# ESP8266_MySensorsGateway_v1_4.net
KiCad netlist of a schematic drawn in EAGLE
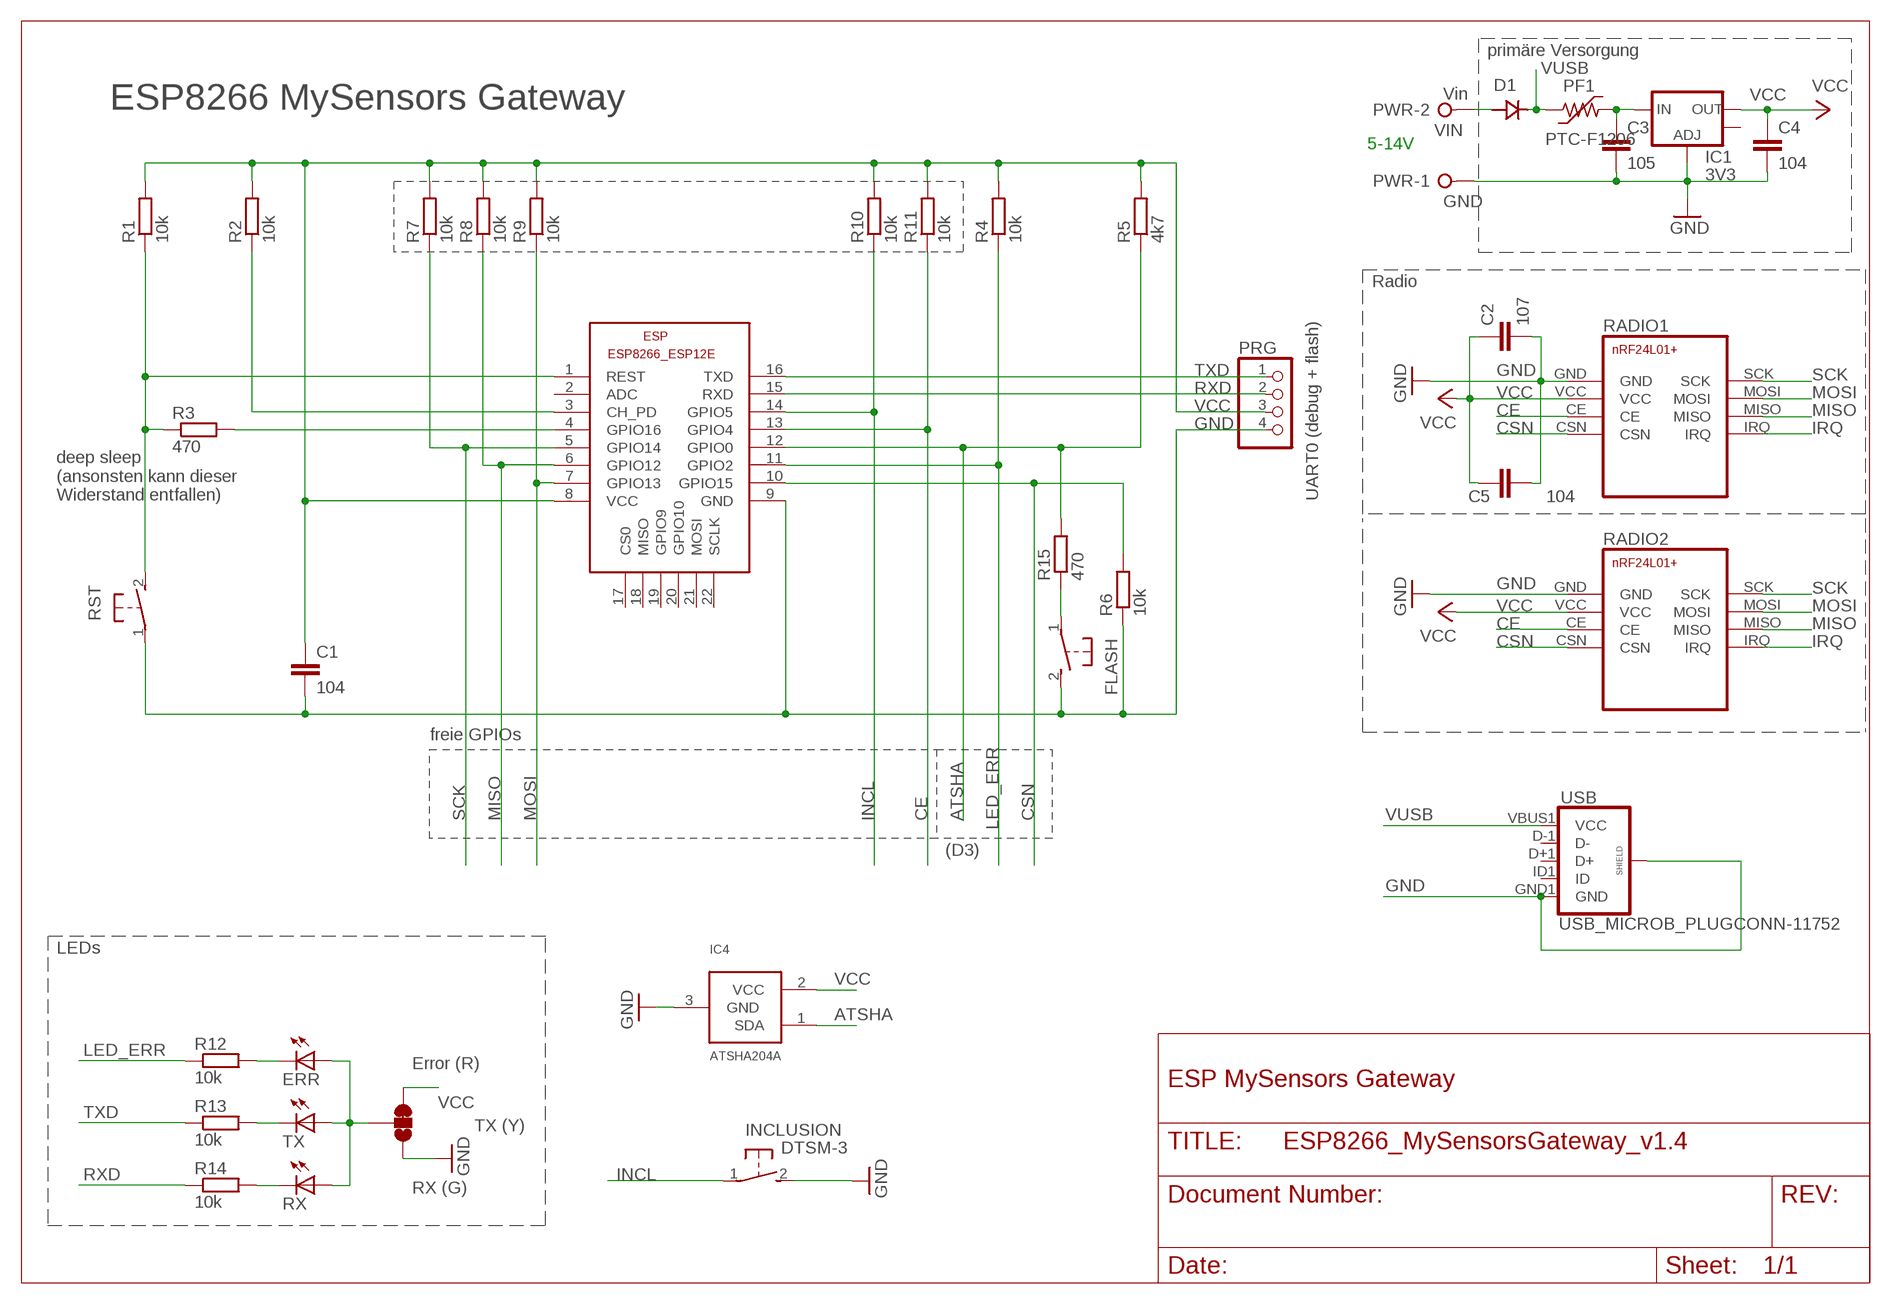
[diagram p0: schematic, sheet 1]

(export (version "E")
  (design (tool "Eeschema 10.0.6"))
  (components
    (comp (ref "C1")
      (value "104")
      (footprint "eagle-import:C0805")
      (libsource (lib "eagle-import") (part "C-EUC0805"))
    )
    (comp (ref "C2")
      (value "107")
      (footprint "eagle-import:MY1210")
      (libsource (lib "eagle-import") (part "C"))
    )
    (comp (ref "C3")
      (value "105")
      (footprint "eagle-import:C0805")
      (libsource (lib "eagle-import") (part "C-EUC0805"))
    )
    (comp (ref "C4")
      (value "104")
      (footprint "eagle-import:C0805")
      (libsource (lib "eagle-import") (part "C-EUC0805"))
    )
    (comp (ref "C5")
      (value "104")
      (footprint "eagle-import:C0805")
      (libsource (lib "eagle-import") (part "C-EUC0805"))
    )
    (comp (ref "D1")
      (value "SS14")
      (footprint "eagle-import:DO214")
      (libsource (lib "eagle-import") (part "SS14"))
    )
    (comp (ref "ERR")
      (value "R")
      (footprint "eagle-import:CHIPLED_1206")
      (libsource (lib "eagle-import") (part "LEDCHIPLED_1206"))
    )
    (comp (ref "ESP")
      (value "µC")
      (footprint "eagle-import:ESP8266-ESP12E")
      (libsource (lib "eagle-import") (part "ESP8266-12EESP8266-ESP12E"))
    )
    (comp (ref "FLASH")
      (value "DTSM-3")
      (footprint "eagle-import:DTSM-3")
      (libsource (lib "eagle-import") (part "DTSM-3"))
    )
    (comp (ref "IC1")
      (value "3V3")
      (footprint "eagle-import:SOT223")
      (libsource (lib "eagle-import") (part "V_REG_LM1117SOT223"))
    )
    (comp (ref "IC4")
      (value "ATSHA204A")
      (footprint "eagle-import:SOT23")
      (libsource (lib "eagle-import") (part "ATSHA204A"))
    )
    (comp (ref "INCLUSION")
      (value "DTSM-3")
      (footprint "eagle-import:DTSM-3")
      (libsource (lib "eagle-import") (part "DTSM-3"))
    )
    (comp (ref "PF1")
      (value "PTC-F1206")
      (footprint "eagle-import:F1206")
      (libsource (lib "eagle-import") (part "PTC-F1206"))
    )
    (comp (ref "PRG")
      (value "PINHD-1X4_S")
      (footprint "eagle-import:1X04")
      (libsource (lib "eagle-import") (part "PINHD-1X4_S"))
    )
    (comp (ref "PWR")
      (value "Vin")
      (footprint "eagle-import:W237-132")
      (libsource (lib "eagle-import") (part "W237-02P"))
    )
    (comp (ref "R1")
      (value "10k")
      (footprint "eagle-import:R0805")
      (libsource (lib "eagle-import") (part "resistor_R-EU_R0805"))
    )
    (comp (ref "R2")
      (value "10k")
      (footprint "eagle-import:R0805")
      (libsource (lib "eagle-import") (part "resistor_R-EU_R0805"))
    )
    (comp (ref "R3")
      (value "470")
      (footprint "eagle-import:R0805")
      (libsource (lib "eagle-import") (part "resistor_R-EU_R0805"))
    )
    (comp (ref "R4")
      (value "10k")
      (footprint "eagle-import:R0805")
      (libsource (lib "eagle-import") (part "resistor_R-EU_R0805"))
    )
    (comp (ref "R5")
      (value "4k7")
      (footprint "eagle-import:R0805")
      (libsource (lib "eagle-import") (part "resistor_R-EU_R0805"))
    )
    (comp (ref "R6")
      (value "10k")
      (footprint "eagle-import:R0805")
      (libsource (lib "eagle-import") (part "resistor_R-EU_R0805"))
    )
    (comp (ref "R7")
      (value "10k")
      (footprint "eagle-import:R0805")
      (libsource (lib "eagle-import") (part "resistor_R-EU_R0805"))
    )
    (comp (ref "R8")
      (value "10k")
      (footprint "eagle-import:R0805")
      (libsource (lib "eagle-import") (part "resistor_R-EU_R0805"))
    )
    (comp (ref "R9")
      (value "10k")
      (footprint "eagle-import:R0805")
      (libsource (lib "eagle-import") (part "resistor_R-EU_R0805"))
    )
    (comp (ref "R10")
      (value "10k")
      (footprint "eagle-import:R0805")
      (libsource (lib "eagle-import") (part "resistor_R-EU_R0805"))
    )
    (comp (ref "R11")
      (value "10k")
      (footprint "eagle-import:R0805")
      (libsource (lib "eagle-import") (part "resistor_R-EU_R0805"))
    )
    (comp (ref "R12")
      (value "10k")
      (footprint "eagle-import:R0805")
      (libsource (lib "eagle-import") (part "R-EU_R0805"))
    )
    (comp (ref "R13")
      (value "10k")
      (footprint "eagle-import:R0805")
      (libsource (lib "eagle-import") (part "R-EU_R0805"))
    )
    (comp (ref "R14")
      (value "10k")
      (footprint "eagle-import:R0805")
      (libsource (lib "eagle-import") (part "R-EU_R0805"))
    )
    (comp (ref "R15")
      (value "470")
      (footprint "eagle-import:R0805")
      (libsource (lib "eagle-import") (part "resistor_R-EU_R0805"))
    )
    (comp (ref "RADIO1")
      (value "NRF24L01+")
      (footprint "eagle-import:NRF24L01+")
      (libsource (lib "eagle-import") (part "NRF24L01+"))
    )
    (comp (ref "RADIO2")
      (value "NRF24L01+NRF24L01+MINI")
      (footprint "eagle-import:NRF24L01+MINI")
      (libsource (lib "eagle-import") (part "NRF24L01+NRF24L01+MINI"))
    )
    (comp (ref "RST")
      (value "DTSM-3")
      (footprint "eagle-import:DTSM-3")
      (libsource (lib "eagle-import") (part "DTSM-3"))
    )
    (comp (ref "RX")
      (value "G")
      (footprint "eagle-import:CHIPLED_1206")
      (libsource (lib "eagle-import") (part "LEDCHIPLED_1206"))
    )
    (comp (ref "SJ1")
      (value "JUMPER-PAD-3-2OF3_NC_BY_TRACE_SMALL")
      (footprint "eagle-import:PAD-JUMPER-3-2OF3_NC_BY_TRACE_YES_SILK_FULL_BOX")
      (libsource (lib "eagle-import") (part "JUMPER-PAD-3-2OF3_NC_BY_TRACE_SMALL"))
    )
    (comp (ref "TX")
      (value "Y")
      (footprint "eagle-import:CHIPLED_1206")
      (libsource (lib "eagle-import") (part "LEDCHIPLED_1206"))
    )
    (comp (ref "USB")
      (value "USB_MICROB_PLUGCONN-11752")
      (footprint "eagle-import:USB-B-MICRO-SMD_V03")
      (libsource (lib "eagle-import") (part "USB_MICROB_PLUGCONN-11752"))
    )
  )
  (nets
    (net (code "1") (name "/ATSHA") (class "Default")
      (node (ref "ESP") (pin "12") (pinfunction "GPIO0_12") (pintype "bidirectional"))
      (node (ref "IC4") (pin "1") (pinfunction "SDA_1") (pintype "bidirectional"))
      (node (ref "R15") (pin "2") (pinfunction "2_2") (pintype "passive"))
      (node (ref "R5") (pin "1") (pinfunction "1_1") (pintype "passive"))
    )
    (net (code "2") (name "/CE") (class "Default")
      (node (ref "ESP") (pin "13") (pinfunction "GPIO4_13") (pintype "bidirectional"))
      (node (ref "R11") (pin "1") (pinfunction "1_1") (pintype "passive"))
      (node (ref "RADIO1") (pin "CE") (pinfunction "CE_CE") (pintype "bidirectional"))
      (node (ref "RADIO2") (pin "CE") (pinfunction "CE_CE") (pintype "bidirectional"))
    )
    (net (code "3") (name "/CSN") (class "Default")
      (node (ref "ESP") (pin "10") (pinfunction "GPIO15_10") (pintype "bidirectional"))
      (node (ref "R6") (pin "2") (pinfunction "2_2") (pintype "passive"))
      (node (ref "RADIO1") (pin "CSN") (pinfunction "CSN_CSN") (pintype "bidirectional"))
      (node (ref "RADIO2") (pin "CSN") (pinfunction "CSN_CSN") (pintype "bidirectional"))
    )
    (net (code "4") (name "/INCL") (class "Default")
      (node (ref "ESP") (pin "14") (pinfunction "GPIO5_14") (pintype "bidirectional"))
      (node (ref "INCLUSION") (pin "1") (pinfunction "1_1") (pintype "passive"))
      (node (ref "R10") (pin "1") (pinfunction "1_1") (pintype "passive"))
    )
    (net (code "5") (name "/IRQ") (class "Default")
      (node (ref "RADIO1") (pin "IRQ") (pinfunction "IRQ_IRQ") (pintype "bidirectional"))
      (node (ref "RADIO2") (pin "IRQ") (pinfunction "IRQ_IRQ") (pintype "bidirectional"))
    )
    (net (code "6") (name "/LED_ERR") (class "Default")
      (node (ref "ESP") (pin "11") (pinfunction "GPIO2_11") (pintype "bidirectional"))
      (node (ref "R12") (pin "1") (pinfunction "1_1") (pintype "passive"))
      (node (ref "R4") (pin "1") (pinfunction "1_1") (pintype "passive"))
    )
    (net (code "7") (name "/MISO") (class "Default")
      (node (ref "ESP") (pin "6") (pinfunction "GPIO12_6") (pintype "bidirectional"))
      (node (ref "R8") (pin "1") (pinfunction "1_1") (pintype "passive"))
      (node (ref "RADIO1") (pin "MISO") (pinfunction "MISO_MISO") (pintype "bidirectional"))
      (node (ref "RADIO2") (pin "MISO") (pinfunction "MISO_MISO") (pintype "bidirectional"))
    )
    (net (code "8") (name "/MOSI") (class "Default")
      (node (ref "ESP") (pin "7") (pinfunction "GPIO13_7") (pintype "bidirectional"))
      (node (ref "R9") (pin "1") (pinfunction "1_1") (pintype "passive"))
      (node (ref "RADIO1") (pin "MOSI") (pinfunction "MOSI_MOSI") (pintype "bidirectional"))
      (node (ref "RADIO2") (pin "MOSI") (pinfunction "MOSI_MOSI") (pintype "bidirectional"))
    )
    (net (code "9") (name "/RXD") (class "Default")
      (node (ref "ESP") (pin "15") (pinfunction "RXD_15") (pintype "bidirectional"))
      (node (ref "PRG") (pin "2") (pinfunction "2_2") (pintype "passive"))
      (node (ref "R14") (pin "1") (pinfunction "1_1") (pintype "passive"))
    )
    (net (code "10") (name "/SCK") (class "Default")
      (node (ref "ESP") (pin "5") (pinfunction "GPIO14_5") (pintype "bidirectional"))
      (node (ref "R7") (pin "1") (pinfunction "1_1") (pintype "passive"))
      (node (ref "RADIO1") (pin "SCK") (pinfunction "SCK_SCK") (pintype "bidirectional"))
      (node (ref "RADIO2") (pin "SCK") (pinfunction "SCK_SCK") (pintype "bidirectional"))
    )
    (net (code "11") (name "/TXD") (class "Default")
      (node (ref "ESP") (pin "16") (pinfunction "TXD_16") (pintype "bidirectional"))
      (node (ref "PRG") (pin "1") (pinfunction "1_1") (pintype "passive"))
      (node (ref "R13") (pin "1") (pinfunction "1_1") (pintype "passive"))
    )
    (net (code "12") (name "/VIN") (class "Default")
      (node (ref "D1") (pin "ANODE") (pinfunction "ANODE_ANODE") (pintype "bidirectional"))
      (node (ref "PWR") (pin "2") (pinfunction "KL_2") (pintype "passive"))
    )
    (net (code "13") (name "/VUSB") (class "Default")
      (node (ref "D1") (pin "CATHODE") (pinfunction "CATHODE_CATHODE") (pintype "bidirectional"))
      (node (ref "PF1") (pin "1") (pinfunction "1_1") (pintype "passive"))
      (node (ref "USB") (pin "VBUS1") (pinfunction "VCC_VBUS1") (pintype "bidirectional"))
    )
    (net (code "14") (name "GND") (class "Default")
      (node (ref "C1") (pin "2") (pinfunction "2_2") (pintype "passive"))
      (node (ref "C2") (pin "2") (pinfunction "2_2") (pintype "passive"))
      (node (ref "C3") (pin "2") (pinfunction "2_2") (pintype "passive"))
      (node (ref "C4") (pin "2") (pinfunction "2_2") (pintype "passive"))
      (node (ref "C5") (pin "2") (pinfunction "2_2") (pintype "passive"))
      (node (ref "ESP") (pin "9") (pinfunction "GND_9") (pintype "bidirectional"))
      (node (ref "FLASH") (pin "2") (pinfunction "2_2") (pintype "passive"))
      (node (ref "IC1") (pin "1") (pinfunction "ADJ_1") (pintype "input"))
      (node (ref "IC4") (pin "3") (pinfunction "GND_3") (pintype "bidirectional"))
      (node (ref "INCLUSION") (pin "2") (pinfunction "2_2") (pintype "passive"))
      (node (ref "PRG") (pin "4") (pinfunction "4_4") (pintype "passive"))
      (node (ref "PWR") (pin "1") (pinfunction "KL_1") (pintype "passive"))
      (node (ref "R6") (pin "1") (pinfunction "1_1") (pintype "passive"))
      (node (ref "RADIO1") (pin "GND") (pinfunction "GND_GND") (pintype "power_in"))
      (node (ref "RADIO2") (pin "GND") (pinfunction "GND_GND") (pintype "power_in"))
      (node (ref "RST") (pin "1") (pinfunction "1_1") (pintype "passive"))
      (node (ref "SJ1") (pin "1") (pinfunction "1_1") (pintype "passive"))
      (node (ref "USB") (pin "GND1") (pinfunction "GND_GND1") (pintype "bidirectional"))
      (node (ref "USB") (pin "SHIELD1") (pinfunction "SHIELD_SHIELD1") (pintype "bidirectional"))
      (node (ref "USB") (pin "SHIELD2") (pinfunction "SHIELD_SHIELD2") (pintype "bidirectional"))
      (node (ref "USB") (pin "SHIELD3") (pinfunction "SHIELD_SHIELD3") (pintype "bidirectional"))
    )
    (net (code "15") (name "Net-(ERR-PadA)") (class "Default")
      (node (ref "ERR") (pin "A") (pinfunction "A_A") (pintype "passive"))
      (node (ref "RX") (pin "A") (pinfunction "A_A") (pintype "passive"))
      (node (ref "SJ1") (pin "2") (pinfunction "2_2") (pintype "passive"))
      (node (ref "TX") (pin "A") (pinfunction "A_A") (pintype "passive"))
    )
    (net (code "16") (name "Net-(ERR-PadC)") (class "Default")
      (node (ref "ERR") (pin "C") (pinfunction "C_C") (pintype "passive"))
      (node (ref "R12") (pin "2") (pinfunction "2_2") (pintype "passive"))
    )
    (net (code "17") (name "Net-(ESP-CH_PD)") (class "Default")
      (node (ref "ESP") (pin "3") (pinfunction "CH_PD_3") (pintype "bidirectional"))
      (node (ref "R2") (pin "1") (pinfunction "1_1") (pintype "passive"))
    )
    (net (code "18") (name "Net-(ESP-GPIO16)") (class "Default")
      (node (ref "ESP") (pin "4") (pinfunction "GPIO16_4") (pintype "bidirectional"))
      (node (ref "R3") (pin "2") (pinfunction "2_2") (pintype "passive"))
    )
    (net (code "19") (name "Net-(ESP-REST)") (class "Default")
      (node (ref "ESP") (pin "1") (pinfunction "REST_1") (pintype "bidirectional"))
      (node (ref "R1") (pin "1") (pinfunction "1_1") (pintype "passive"))
      (node (ref "R3") (pin "1") (pinfunction "1_1") (pintype "passive"))
      (node (ref "RST") (pin "2") (pinfunction "2_2") (pintype "passive"))
    )
    (net (code "20") (name "Net-(FLASH-Pad1)") (class "Default")
      (node (ref "FLASH") (pin "1") (pinfunction "1_1") (pintype "passive"))
      (node (ref "R15") (pin "1") (pinfunction "1_1") (pintype "passive"))
    )
    (net (code "21") (name "Net-(IC1-IN)") (class "Default")
      (node (ref "C3") (pin "1") (pinfunction "1_1") (pintype "passive"))
      (node (ref "IC1") (pin "3") (pinfunction "IN_3") (pintype "input"))
      (node (ref "PF1") (pin "2") (pinfunction "2_2") (pintype "passive"))
    )
    (net (code "22") (name "Net-(R13-Pad2)") (class "Default")
      (node (ref "R13") (pin "2") (pinfunction "2_2") (pintype "passive"))
      (node (ref "TX") (pin "C") (pinfunction "C_C") (pintype "passive"))
    )
    (net (code "23") (name "Net-(R14-Pad2)") (class "Default")
      (node (ref "R14") (pin "2") (pinfunction "2_2") (pintype "passive"))
      (node (ref "RX") (pin "C") (pinfunction "C_C") (pintype "passive"))
    )
    (net (code "24") (name "VCC") (class "Default")
      (node (ref "C1") (pin "1") (pinfunction "1_1") (pintype "passive"))
      (node (ref "C2") (pin "1") (pinfunction "1_1") (pintype "passive"))
      (node (ref "C4") (pin "1") (pinfunction "1_1") (pintype "passive"))
      (node (ref "C5") (pin "1") (pinfunction "1_1") (pintype "passive"))
      (node (ref "ESP") (pin "8") (pinfunction "VCC_8") (pintype "bidirectional"))
      (node (ref "IC1") (pin "2") (pinfunction "OUT_2") (pintype "output"))
      (node (ref "IC4") (pin "2") (pinfunction "VCC_2") (pintype "bidirectional"))
      (node (ref "PRG") (pin "3") (pinfunction "3_3") (pintype "passive"))
      (node (ref "R1") (pin "2") (pinfunction "2_2") (pintype "passive"))
      (node (ref "R10") (pin "2") (pinfunction "2_2") (pintype "passive"))
      (node (ref "R11") (pin "2") (pinfunction "2_2") (pintype "passive"))
      (node (ref "R2") (pin "2") (pinfunction "2_2") (pintype "passive"))
      (node (ref "R4") (pin "2") (pinfunction "2_2") (pintype "passive"))
      (node (ref "R5") (pin "2") (pinfunction "2_2") (pintype "passive"))
      (node (ref "R7") (pin "2") (pinfunction "2_2") (pintype "passive"))
      (node (ref "R8") (pin "2") (pinfunction "2_2") (pintype "passive"))
      (node (ref "R9") (pin "2") (pinfunction "2_2") (pintype "passive"))
      (node (ref "RADIO1") (pin "VCC") (pinfunction "VCC_VCC") (pintype "power_in"))
      (node (ref "RADIO2") (pin "VCC") (pinfunction "VCC_VCC") (pintype "power_in"))
      (node (ref "SJ1") (pin "3") (pinfunction "3_3") (pintype "passive"))
    )
    (net (code "25") (name "unconnected-(ESP-ADC-Pad2)") (class "Default")
      (node (ref "ESP") (pin "2") (pinfunction "ADC_2") (pintype "bidirectional"))
    )
    (net (code "26") (name "unconnected-(ESP-CS0-Pad17)") (class "Default")
      (node (ref "ESP") (pin "17") (pinfunction "CS0_17") (pintype "bidirectional"))
    )
    (net (code "27") (name "unconnected-(ESP-GPIO9-Pad19)") (class "Default")
      (node (ref "ESP") (pin "19") (pinfunction "GPIO9_19") (pintype "bidirectional"))
    )
    (net (code "28") (name "unconnected-(ESP-GPIO10-Pad20)") (class "Default")
      (node (ref "ESP") (pin "20") (pinfunction "GPIO10_20") (pintype "bidirectional"))
    )
    (net (code "29") (name "unconnected-(ESP-MISO-Pad18)") (class "Default")
      (node (ref "ESP") (pin "18") (pinfunction "MISO_18") (pintype "bidirectional"))
    )
    (net (code "30") (name "unconnected-(ESP-MOSI-Pad21)") (class "Default")
      (node (ref "ESP") (pin "21") (pinfunction "MOSI_21") (pintype "bidirectional"))
    )
    (net (code "31") (name "unconnected-(ESP-SCLK-Pad22)") (class "Default")
      (node (ref "ESP") (pin "22") (pinfunction "SCLK_22") (pintype "bidirectional"))
    )
    (net (code "32") (name "unconnected-(IC1-OUT-Pad4)") (class "Default")
      (node (ref "IC1") (pin "4") (pinfunction "OUT_4") (pintype "output"))
    )
    (net (code "33") (name "unconnected-(USB-D+-PadD+1)") (class "Default")
      (node (ref "USB") (pin "D+1") (pinfunction "D+_D+1") (pintype "bidirectional"))
    )
    (net (code "34") (name "unconnected-(USB-D--PadD-1)") (class "Default")
      (node (ref "USB") (pin "D-1") (pinfunction "D-_D-1") (pintype "bidirectional"))
    )
    (net (code "35") (name "unconnected-(USB-ID-PadID1)") (class "Default")
      (node (ref "USB") (pin "ID1") (pinfunction "ID_ID1") (pintype "bidirectional"))
    )
  )
)
